# Power.net
KiCad netlist of a schematic drawn in Altium Designer
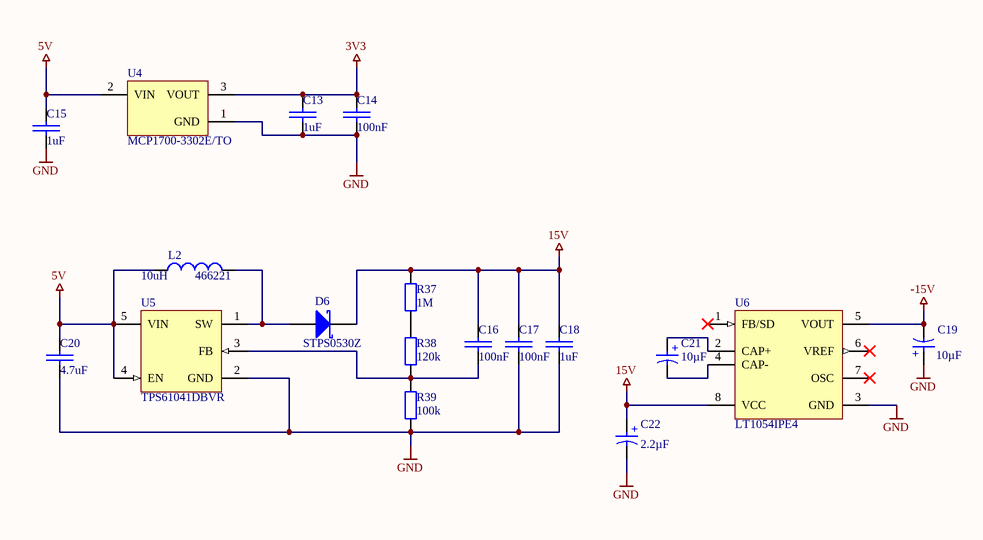
[diagram p0: Power.SchDoc]

(export (version "E")
  (design (tool "Eeschema 10.0.6"))
  (components
    (comp (ref "C13") (value "1uF") (footprint "Cap_0805") (libsource (lib "*") (part "C")))
    (comp (ref "C14") (value "100nF") (footprint "Cap_0805") (libsource (lib "*") (part "C")))
    (comp (ref "C15") (value "1uF") (footprint "Cap_0805") (libsource (lib "*") (part "C")))
    (comp (ref "C16") (value "100nF") (footprint "Cap_0805") (libsource (lib "*") (part "C")))
    (comp (ref "C17") (value "100nF") (footprint "Cap_0805") (libsource (lib "*") (part "C")))
    (comp (ref "C18") (value "1uF") (footprint "Cap_0805") (libsource (lib "*") (part "C")))
    (comp (ref "C19")
      (value "865080642006")
      (footprint "WCAP-ASLI_D5H5.5")
      (description "Alum. Electrolytic Cap 10UF 50V, 5MM Surface Mount, Lifetime 2000H, +105OC")
      (fields (field (name "TOLERANCE") "20%") (field (name "CAPACITANCE") "10µF"))
      (libsource (lib "Altium Content Vault") (part "Capacitor_Polarized"))
    )
    (comp (ref "C20") (value "4.7uF") (footprint "Cap_0805") (libsource (lib "*") (part "C")))
    (comp (ref "C21")
      (value "865080642006")
      (footprint "WCAP-ASLI_D5H5.5")
      (description "Alum. Electrolytic Cap 10UF 50V, 5MM Surface Mount, Lifetime 2000H, +105OC")
      (fields (field (name "TOLERANCE") "20%") (field (name "CAPACITANCE") "10µF"))
      (libsource (lib "Altium Content Vault") (part "Capacitor_Polarized"))
    )
    (comp (ref "C22")
      (value "865060640002")
      (footprint "WCAP-ASLL_D4H5.5")
      (description "WCAP-ASLL Aluminum Electrolytic Capacitors")
      (fields (field (name "CAPACITANCE") "2.2µF") (field (name "TOLERANCE") "20%"))
      (libsource (lib "Altium Content Vault") (part "Capacitor_Polarized"))
    )
    (comp (ref "D6") (value "STPS0530Z") (footprint "SOD-123") (libsource (lib "AZR-LIB") (part "STPS0530Z")))
    (comp (ref "L2")
      (value "10uH")
      (footprint "SRN3015C")
      (description "Inductor")
      (fields (field (name "SUPPLIER PART NUMBER 1") "466221") (field (name "PUBLISHER") "Altium Limited"))
      (libsource (lib "Miscellaneous Devices") (part "Inductor"))
    )
    (comp (ref "R37")
      (value "1M")
      (footprint "RES_0805")
      (description "Res 0805")
      (fields (field (name "PART NUMBER") "ERJ6ENF2703V") (field (name "MANUFACTURER") "Panasonic"))
      (libsource (lib "2121_Robot3roues_V2.0") (part "RES"))
    )
    (comp (ref "R38")
      (value "120k")
      (footprint "RES_0805")
      (description "Res 0805")
      (fields (field (name "PART NUMBER") "ERJ6ENF2703V") (field (name "MANUFACTURER") "Panasonic"))
      (libsource (lib "2121_Robot3roues_V2.0") (part "RES"))
    )
    (comp (ref "R39")
      (value "100k")
      (footprint "RES_0805")
      (description "Res 0805")
      (fields (field (name "PART NUMBER") "ERJ6ENF2703V") (field (name "MANUFACTURER") "Panasonic"))
      (libsource (lib "2121_Robot3roues_V2.0") (part "RES"))
    )
    (comp (ref "U4")
      (value "MCP1700-3302E/TO")
      (footprint "TO-92-TO3")
      (description "Low Quiescent Current LDO, 3-Pin TO-92, Extended TemperatureBAG")
      (libsource (lib "Altium Content Vault") (part "PM-LINEREG-MCP1700-IL3B"))
    )
    (comp (ref "U5")
      (value "TPS61041DBVR")
      (footprint "DBV0005A_M")
      (fields (field (name "MANUFACTURER") "Texas Instruments"))
      (libsource (lib "Altium Content Vault") (part "TI-TPS61041DBV5"))
    )
    (comp (ref "U6")
      (value "LT1054IPE4")
      (footprint "TI-P8")
      (fields (field (name "MANUFACTURER") "Texas Instruments"))
      (libsource (lib "Altium Content Vault") (part "TI-1054P8"))
    )
  )
  (nets
    (net (code "1") (name "-15V") (class "Default")
      (node (ref "C19") (pin "2") (pinfunction "N_2") (pintype "passive"))
      (node (ref "U6") (pin "5") (pinfunction "VOUT_5") (pintype "power_in"))
    )
    (net (code "2") (name "3V3") (class "Default")
      (node (ref "C13") (pin "1") (pinfunction "1_1") (pintype "passive"))
      (node (ref "C14") (pin "1") (pinfunction "1_1") (pintype "passive"))
      (node (ref "U4") (pin "3") (pinfunction "VOUT_3") (pintype "power_in"))
    )
    (net (code "3") (name "5V") (class "Default")
      (node (ref "C15") (pin "1") (pinfunction "1_1") (pintype "passive"))
      (node (ref "C20") (pin "1") (pinfunction "1_1") (pintype "passive"))
      (node (ref "L2") (pin "1") (pinfunction "1_1") (pintype "passive"))
      (node (ref "U4") (pin "2") (pinfunction "VIN_2") (pintype "power_in"))
      (node (ref "U5") (pin "4") (pinfunction "EN_4") (pintype "input"))
      (node (ref "U5") (pin "5") (pinfunction "VIN_5") (pintype "power_in"))
    )
    (net (code "4") (name "15V") (class "Default")
      (node (ref "C16") (pin "1") (pinfunction "1_1") (pintype "passive"))
      (node (ref "C17") (pin "1") (pinfunction "1_1") (pintype "passive"))
      (node (ref "C18") (pin "1") (pinfunction "1_1") (pintype "passive"))
      (node (ref "C22") (pin "1") (pinfunction "P_1") (pintype "passive"))
      (node (ref "D6") (pin "K") (pinfunction "K_K") (pintype "passive"))
      (node (ref "R37") (pin "1") (pinfunction "1_1") (pintype "passive"))
      (node (ref "U6") (pin "8") (pinfunction "VCC_8") (pintype "power_in"))
    )
    (net (code "5") (name "GND") (class "Default")
      (node (ref "C13") (pin "2") (pinfunction "2_2") (pintype "passive"))
      (node (ref "C14") (pin "2") (pinfunction "2_2") (pintype "passive"))
      (node (ref "C15") (pin "2") (pinfunction "2_2") (pintype "passive"))
      (node (ref "C17") (pin "2") (pinfunction "2_2") (pintype "passive"))
      (node (ref "C18") (pin "2") (pinfunction "2_2") (pintype "passive"))
      (node (ref "C19") (pin "1") (pinfunction "P_1") (pintype "passive"))
      (node (ref "C20") (pin "2") (pinfunction "2_2") (pintype "passive"))
      (node (ref "C22") (pin "2") (pinfunction "N_2") (pintype "passive"))
      (node (ref "R39") (pin "2") (pinfunction "2_2") (pintype "passive"))
      (node (ref "U4") (pin "1") (pinfunction "GND_1") (pintype "power_in"))
      (node (ref "U5") (pin "2") (pinfunction "GND_2") (pintype "power_in"))
      (node (ref "U6") (pin "3") (pinfunction "GND_3") (pintype "power_in"))
    )
    (net (code "6") (name "Net-(C21-N)") (class "Default")
      (node (ref "C21") (pin "2") (pinfunction "N_2") (pintype "passive"))
      (node (ref "U6") (pin "4") (pinfunction "CAP-_4") (pintype "passive"))
    )
    (net (code "7") (name "Net-(C21-P)") (class "Default")
      (node (ref "C21") (pin "1") (pinfunction "P_1") (pintype "passive"))
      (node (ref "U6") (pin "2") (pinfunction "CAP+_2") (pintype "passive"))
    )
    (net (code "8") (name "Net-(R37-Pad2)") (class "Default")
      (node (ref "R37") (pin "2") (pinfunction "2_2") (pintype "passive"))
      (node (ref "R38") (pin "1") (pinfunction "1_1") (pintype "passive"))
    )
    (net (code "9") (name "Net-(U5-FB)") (class "Default")
      (node (ref "C16") (pin "2") (pinfunction "2_2") (pintype "passive"))
      (node (ref "R38") (pin "2") (pinfunction "2_2") (pintype "passive"))
      (node (ref "R39") (pin "1") (pinfunction "1_1") (pintype "passive"))
      (node (ref "U5") (pin "3") (pinfunction "FB_3") (pintype "input"))
    )
    (net (code "10") (name "Net-(U5-SW)") (class "Default")
      (node (ref "D6") (pin "A") (pinfunction "A_A") (pintype "passive"))
      (node (ref "L2") (pin "2") (pinfunction "2_2") (pintype "passive"))
      (node (ref "U5") (pin "1") (pinfunction "SW_1") (pintype "power_in"))
    )
    (net (code "11") (name "unconnected-(U6-FB{slash}SD-Pad1)") (class "Default")
      (node (ref "U6") (pin "1") (pinfunction "FB/SD_1") (pintype "input+no_connect"))
    )
    (net (code "12") (name "unconnected-(U6-OSC-Pad7)") (class "Default")
      (node (ref "U6") (pin "7") (pinfunction "OSC_7") (pintype "passive+no_connect"))
    )
    (net (code "13") (name "unconnected-(U6-VREF-Pad6)") (class "Default")
      (node (ref "U6") (pin "6") (pinfunction "VREF_6") (pintype "output+no_connect"))
    )
  )
)
